# Basic_arduino.net
KiCad netlist of a schematic drawn in EAGLE
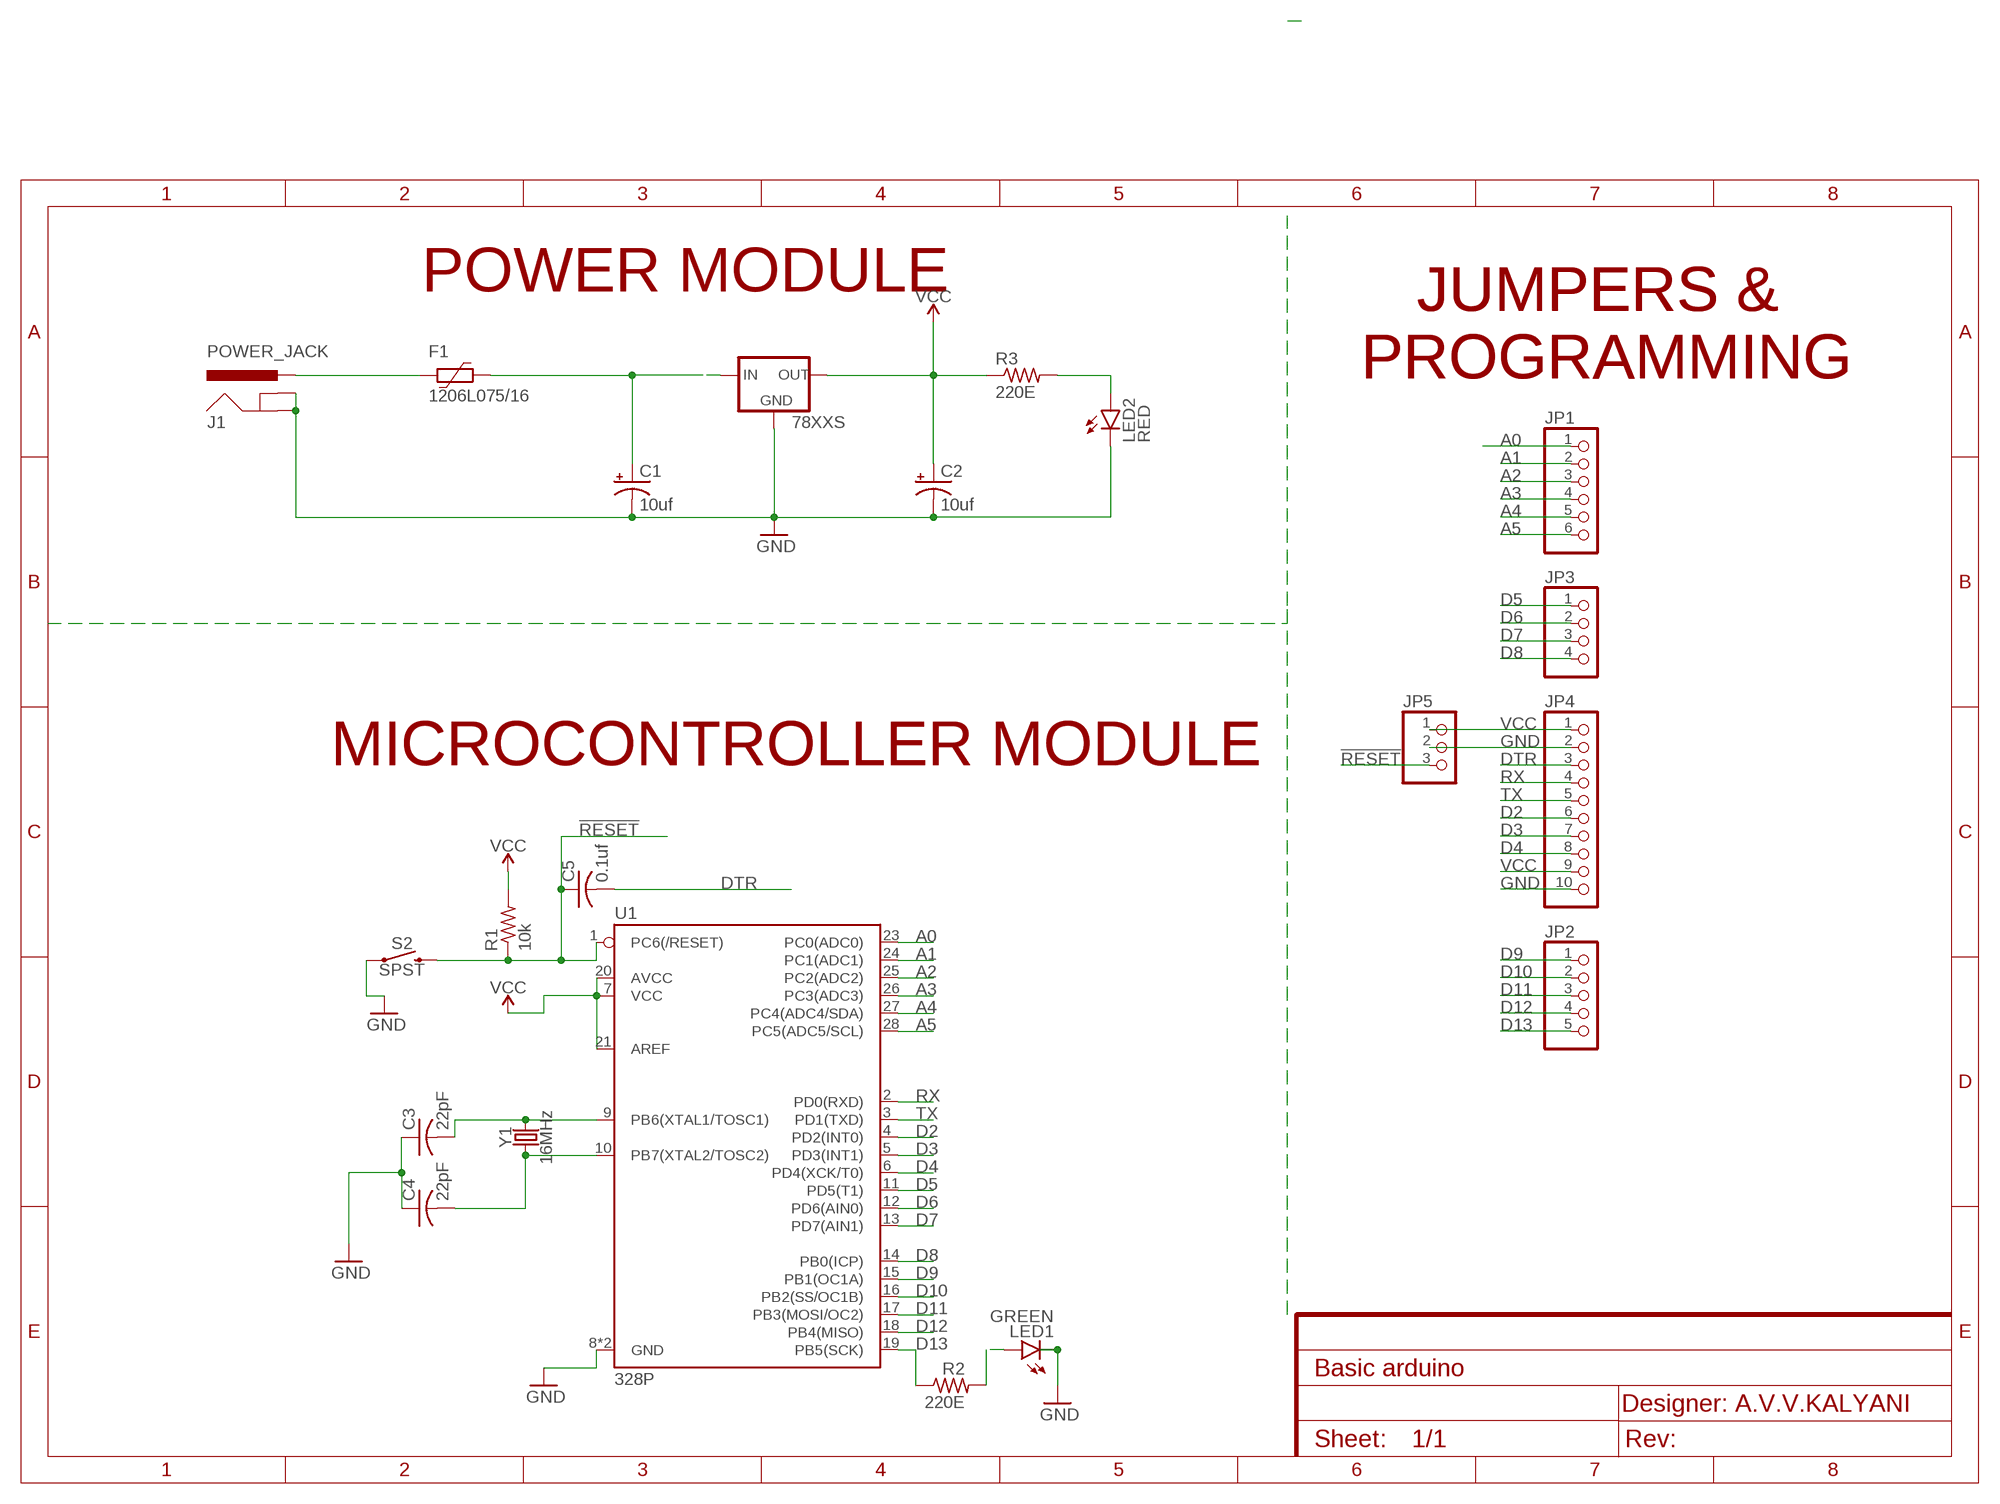
[diagram p0: schematic, sheet 1]

(export (version "E")
  (design (tool "Eeschema 10.0.6"))
  (components
    (comp (ref "78XXS")
      (value "78XXS")
      (footprint "eagle-import:78XXS")
      (libsource (lib "eagle-import") (part "78XXS"))
    )
    (comp (ref "C1")
      (value "10uf")
      (footprint "eagle-import:E2,5-6")
      (libsource (lib "eagle-import") (part "CPOL-USE2.5-6"))
    )
    (comp (ref "C2")
      (value "10uf")
      (footprint "eagle-import:E2,5-6")
      (libsource (lib "eagle-import") (part "CPOL-USE2.5-6"))
    )
    (comp (ref "C3")
      (value "22pF")
      (footprint "eagle-import:C025-025X050")
      (libsource (lib "eagle-import") (part "C-US025-025X050"))
    )
    (comp (ref "C4")
      (value "22pF")
      (footprint "eagle-import:C025-025X050")
      (libsource (lib "eagle-import") (part "C-US025-025X050"))
    )
    (comp (ref "C5")
      (value "0.1uf")
      (footprint "eagle-import:C025-024X044")
      (libsource (lib "eagle-import") (part "C-US025-024X044"))
    )
    (comp (ref "F1")
      (value "1206L075/16")
      (footprint "eagle-import:1206L")
      (fields (field (name "MF") "Littelfuse"))
      (libsource (lib "eagle-import") (part "?1206L075/16"))
    )
    (comp (ref "J1")
      (value "POWER_JACK")
      (footprint "eagle-import:POWER_JACK_PTH")
      (libsource (lib "eagle-import") (part "POWER_JACK"))
    )
    (comp (ref "JP1")
      (value "PINHD-1X6")
      (footprint "eagle-import:1X06")
      (libsource (lib "eagle-import") (part "PINHD-1X6"))
    )
    (comp (ref "JP2")
      (value "PINHD-1X5")
      (footprint "eagle-import:1X05")
      (libsource (lib "eagle-import") (part "PINHD-1X5"))
    )
    (comp (ref "JP3")
      (value "PINHD-1X4")
      (footprint "eagle-import:1X04")
      (libsource (lib "eagle-import") (part "PINHD-1X4"))
    )
    (comp (ref "JP4")
      (value "PINHD-1X10")
      (footprint "eagle-import:1X10")
      (libsource (lib "eagle-import") (part "PINHD-1X10"))
    )
    (comp (ref "JP5")
      (value "PINHD-1X3")
      (footprint "eagle-import:1X03")
      (libsource (lib "eagle-import") (part "PINHD-1X3"))
    )
    (comp (ref "LED1")
      (value "GREEN")
      (footprint "eagle-import:LED3MM")
      (libsource (lib "eagle-import") (part "LED3MM"))
    )
    (comp (ref "LED2")
      (value "RED")
      (footprint "eagle-import:LED3MM")
      (libsource (lib "eagle-import") (part "LED3MM"))
    )
    (comp (ref "R1")
      (value "10k")
      (footprint "eagle-import:0204_7")
      (libsource (lib "eagle-import") (part "R-US_0204/7"))
    )
    (comp (ref "R2")
      (value "220E")
      (footprint "eagle-import:0204_7")
      (libsource (lib "eagle-import") (part "R-US_0204/7"))
    )
    (comp (ref "R3")
      (value "220E")
      (footprint "eagle-import:0204_7")
      (libsource (lib "eagle-import") (part "R-US_0204/7"))
    )
    (comp (ref "S2")
      (value "SPST")
      (footprint "eagle-import:TACTILE_SWITCH_PTH_6.0MM")
      (libsource (lib "eagle-import") (part "MOMENTARY-SWITCH-SPST-PTH-6.0MM"))
    )
    (comp (ref "U1")
      (value "328P")
      (footprint "eagle-import:DIP28")
      (libsource (lib "eagle-import") (part "ATMEGA328P_PDIP"))
    )
    (comp (ref "Y1")
      (value "16MHz")
      (footprint "eagle-import:HC49US")
      (libsource (lib "eagle-import") (part "CRYSTAL-16MHZPTH-HC49US"))
    )
  )
  (nets
    (net (code "1") (name "/A0") (class "Default")
      (node (ref "JP1") (pin "1") (pinfunction "1_1") (pintype "passive"))
      (node (ref "U1") (pin "23") (pinfunction "PC0(ADC0)_23") (pintype "bidirectional"))
    )
    (net (code "2") (name "/A1") (class "Default")
      (node (ref "JP1") (pin "2") (pinfunction "2_2") (pintype "passive"))
      (node (ref "U1") (pin "24") (pinfunction "PC1(ADC1)_24") (pintype "bidirectional"))
    )
    (net (code "3") (name "/A2") (class "Default")
      (node (ref "JP1") (pin "3") (pinfunction "3_3") (pintype "passive"))
      (node (ref "U1") (pin "25") (pinfunction "PC2(ADC2)_25") (pintype "bidirectional"))
    )
    (net (code "4") (name "/A3") (class "Default")
      (node (ref "JP1") (pin "4") (pinfunction "4_4") (pintype "passive"))
      (node (ref "U1") (pin "26") (pinfunction "PC3(ADC3)_26") (pintype "bidirectional"))
    )
    (net (code "5") (name "/A4") (class "Default")
      (node (ref "JP1") (pin "5") (pinfunction "5_5") (pintype "passive"))
      (node (ref "U1") (pin "27") (pinfunction "PC4(ADC4/SDA)_27") (pintype "bidirectional"))
    )
    (net (code "6") (name "/A5") (class "Default")
      (node (ref "JP1") (pin "6") (pinfunction "6_6") (pintype "passive"))
      (node (ref "U1") (pin "28") (pinfunction "PC5(ADC5/SCL)_28") (pintype "bidirectional"))
    )
    (net (code "7") (name "/D2") (class "Default")
      (node (ref "JP4") (pin "6") (pinfunction "6_6") (pintype "passive"))
      (node (ref "U1") (pin "4") (pinfunction "PD2(INT0)_4") (pintype "bidirectional"))
    )
    (net (code "8") (name "/D3") (class "Default")
      (node (ref "JP4") (pin "7") (pinfunction "7_7") (pintype "passive"))
      (node (ref "U1") (pin "5") (pinfunction "PD3(INT1)_5") (pintype "bidirectional"))
    )
    (net (code "9") (name "/D4") (class "Default")
      (node (ref "JP4") (pin "8") (pinfunction "8_8") (pintype "passive"))
      (node (ref "U1") (pin "6") (pinfunction "PD4(XCK/T0)_6") (pintype "bidirectional"))
    )
    (net (code "10") (name "/D5") (class "Default")
      (node (ref "JP3") (pin "1") (pinfunction "1_1") (pintype "passive"))
      (node (ref "U1") (pin "11") (pinfunction "PD5(T1)_11") (pintype "bidirectional"))
    )
    (net (code "11") (name "/D6") (class "Default")
      (node (ref "JP3") (pin "2") (pinfunction "2_2") (pintype "passive"))
      (node (ref "U1") (pin "12") (pinfunction "PD6(AIN0)_12") (pintype "bidirectional"))
    )
    (net (code "12") (name "/D7") (class "Default")
      (node (ref "JP3") (pin "3") (pinfunction "3_3") (pintype "passive"))
      (node (ref "U1") (pin "13") (pinfunction "PD7(AIN1)_13") (pintype "bidirectional"))
    )
    (net (code "13") (name "/D8") (class "Default")
      (node (ref "JP3") (pin "4") (pinfunction "4_4") (pintype "passive"))
      (node (ref "U1") (pin "14") (pinfunction "PB0(ICP)_14") (pintype "bidirectional"))
    )
    (net (code "14") (name "/D9") (class "Default")
      (node (ref "JP2") (pin "1") (pinfunction "1_1") (pintype "passive"))
      (node (ref "U1") (pin "15") (pinfunction "PB1(OC1A)_15") (pintype "bidirectional"))
    )
    (net (code "15") (name "/D10") (class "Default")
      (node (ref "JP2") (pin "2") (pinfunction "2_2") (pintype "passive"))
      (node (ref "U1") (pin "16") (pinfunction "PB2(SS/OC1B)_16") (pintype "bidirectional"))
    )
    (net (code "16") (name "/D11") (class "Default")
      (node (ref "JP2") (pin "3") (pinfunction "3_3") (pintype "passive"))
      (node (ref "U1") (pin "17") (pinfunction "PB3(MOSI/OC2)_17") (pintype "bidirectional"))
    )
    (net (code "17") (name "/D12") (class "Default")
      (node (ref "JP2") (pin "4") (pinfunction "4_4") (pintype "passive"))
      (node (ref "U1") (pin "18") (pinfunction "PB4(MISO)_18") (pintype "bidirectional"))
    )
    (net (code "18") (name "/D13") (class "Default")
      (node (ref "JP2") (pin "5") (pinfunction "5_5") (pintype "passive"))
      (node (ref "R2") (pin "1") (pinfunction "1_1") (pintype "passive"))
      (node (ref "U1") (pin "19") (pinfunction "PB5(SCK)_19") (pintype "bidirectional"))
    )
    (net (code "19") (name "/DTR") (class "Default")
      (node (ref "C5") (pin "2") (pinfunction "2_2") (pintype "passive"))
      (node (ref "JP4") (pin "3") (pinfunction "3_3") (pintype "passive"))
    )
    (net (code "20") (name "/RX") (class "Default")
      (node (ref "JP4") (pin "4") (pinfunction "4_4") (pintype "passive"))
      (node (ref "U1") (pin "2") (pinfunction "PD0(RXD)_2") (pintype "bidirectional"))
    )
    (net (code "21") (name "/TX") (class "Default")
      (node (ref "JP4") (pin "5") (pinfunction "5_5") (pintype "passive"))
      (node (ref "U1") (pin "3") (pinfunction "PD1(TXD)_3") (pintype "bidirectional"))
    )
    (net (code "22") (name "/~{RESET}") (class "Default")
      (node (ref "C5") (pin "1") (pinfunction "1_1") (pintype "passive"))
      (node (ref "JP5") (pin "3") (pinfunction "3_3") (pintype "passive"))
      (node (ref "R1") (pin "1") (pinfunction "1_1") (pintype "passive"))
      (node (ref "S2") (pin "3") (pinfunction "2_3") (pintype "passive"))
      (node (ref "U1") (pin "1") (pinfunction "PC6(/RESET)_1") (pintype "bidirectional"))
    )
    (net (code "23") (name "GND") (class "Default")
      (node (ref "78XXS") (pin "GND") (pinfunction "GND_GND") (pintype "input"))
      (node (ref "C1") (pin "-") (pinfunction "-_-") (pintype "passive"))
      (node (ref "C2") (pin "-") (pinfunction "-_-") (pintype "passive"))
      (node (ref "C3") (pin "1") (pinfunction "1_1") (pintype "passive"))
      (node (ref "C4") (pin "1") (pinfunction "1_1") (pintype "passive"))
      (node (ref "J1") (pin "GND") (pinfunction "GND_GND") (pintype "bidirectional"))
      (node (ref "J1") (pin "GNDBREAK") (pinfunction "GNDBREAK_GNDBREAK") (pintype "bidirectional"))
      (node (ref "JP4") (pin "10") (pinfunction "10_10") (pintype "passive"))
      (node (ref "JP4") (pin "2") (pinfunction "2_2") (pintype "passive"))
      (node (ref "JP5") (pin "2") (pinfunction "2_2") (pintype "passive"))
      (node (ref "LED1") (pin "K") (pinfunction "C_K") (pintype "passive"))
      (node (ref "LED2") (pin "K") (pinfunction "C_K") (pintype "passive"))
      (node (ref "S2") (pin "1") (pinfunction "1_1") (pintype "passive"))
      (node (ref "U1") (pin "22") (pinfunction "GND_22") (pintype "bidirectional"))
      (node (ref "U1") (pin "8") (pinfunction "GND_8") (pintype "bidirectional"))
    )
    (net (code "24") (name "Net-(78XXS-PadIN)") (class "Default")
      (node (ref "78XXS") (pin "IN") (pinfunction "IN_IN") (pintype "input"))
      (node (ref "C1") (pin "+") (pinfunction "+_+") (pintype "passive"))
      (node (ref "F1") (pin "1") (pinfunction "1_1") (pintype "passive"))
    )
    (net (code "25") (name "Net-(F1-Pad2)") (class "Default")
      (node (ref "F1") (pin "2") (pinfunction "2_2") (pintype "passive"))
      (node (ref "J1") (pin "PWR") (pinfunction "PWR_PWR") (pintype "bidirectional"))
    )
    (net (code "26") (name "Net-(LED1-PadA)") (class "Default")
      (node (ref "LED1") (pin "A") (pinfunction "A_A") (pintype "passive"))
      (node (ref "R2") (pin "2") (pinfunction "2_2") (pintype "passive"))
    )
    (net (code "27") (name "Net-(LED2-PadA)") (class "Default")
      (node (ref "LED2") (pin "A") (pinfunction "A_A") (pintype "passive"))
      (node (ref "R3") (pin "2") (pinfunction "2_2") (pintype "passive"))
    )
    (net (code "28") (name "Net-(U1-PB6(XTAL1{slash}TOSC1))") (class "Default")
      (node (ref "C3") (pin "2") (pinfunction "2_2") (pintype "passive"))
      (node (ref "U1") (pin "9") (pinfunction "PB6(XTAL1/TOSC1)_9") (pintype "bidirectional"))
      (node (ref "Y1") (pin "2") (pinfunction "2_2") (pintype "passive"))
    )
    (net (code "29") (name "Net-(U1-PB7(XTAL2{slash}TOSC2))") (class "Default")
      (node (ref "C4") (pin "2") (pinfunction "2_2") (pintype "passive"))
      (node (ref "U1") (pin "10") (pinfunction "PB7(XTAL2/TOSC2)_10") (pintype "bidirectional"))
      (node (ref "Y1") (pin "1") (pinfunction "1_1") (pintype "passive"))
    )
    (net (code "30") (name "VCC") (class "Default")
      (node (ref "78XXS") (pin "OUT") (pinfunction "OUT_OUT") (pintype "passive"))
      (node (ref "C2") (pin "+") (pinfunction "+_+") (pintype "passive"))
      (node (ref "JP4") (pin "1") (pinfunction "1_1") (pintype "passive"))
      (node (ref "JP4") (pin "9") (pinfunction "9_9") (pintype "passive"))
      (node (ref "JP5") (pin "1") (pinfunction "1_1") (pintype "passive"))
      (node (ref "R1") (pin "2") (pinfunction "2_2") (pintype "passive"))
      (node (ref "R3") (pin "1") (pinfunction "1_1") (pintype "passive"))
      (node (ref "U1") (pin "20") (pinfunction "AVCC_20") (pintype "bidirectional"))
      (node (ref "U1") (pin "21") (pinfunction "AREF_21") (pintype "bidirectional"))
      (node (ref "U1") (pin "7") (pinfunction "VCC_7") (pintype "bidirectional"))
    )
  )
)
